# XBP-ST_morpho.net
KiCad netlist of a schematic drawn in EAGLE
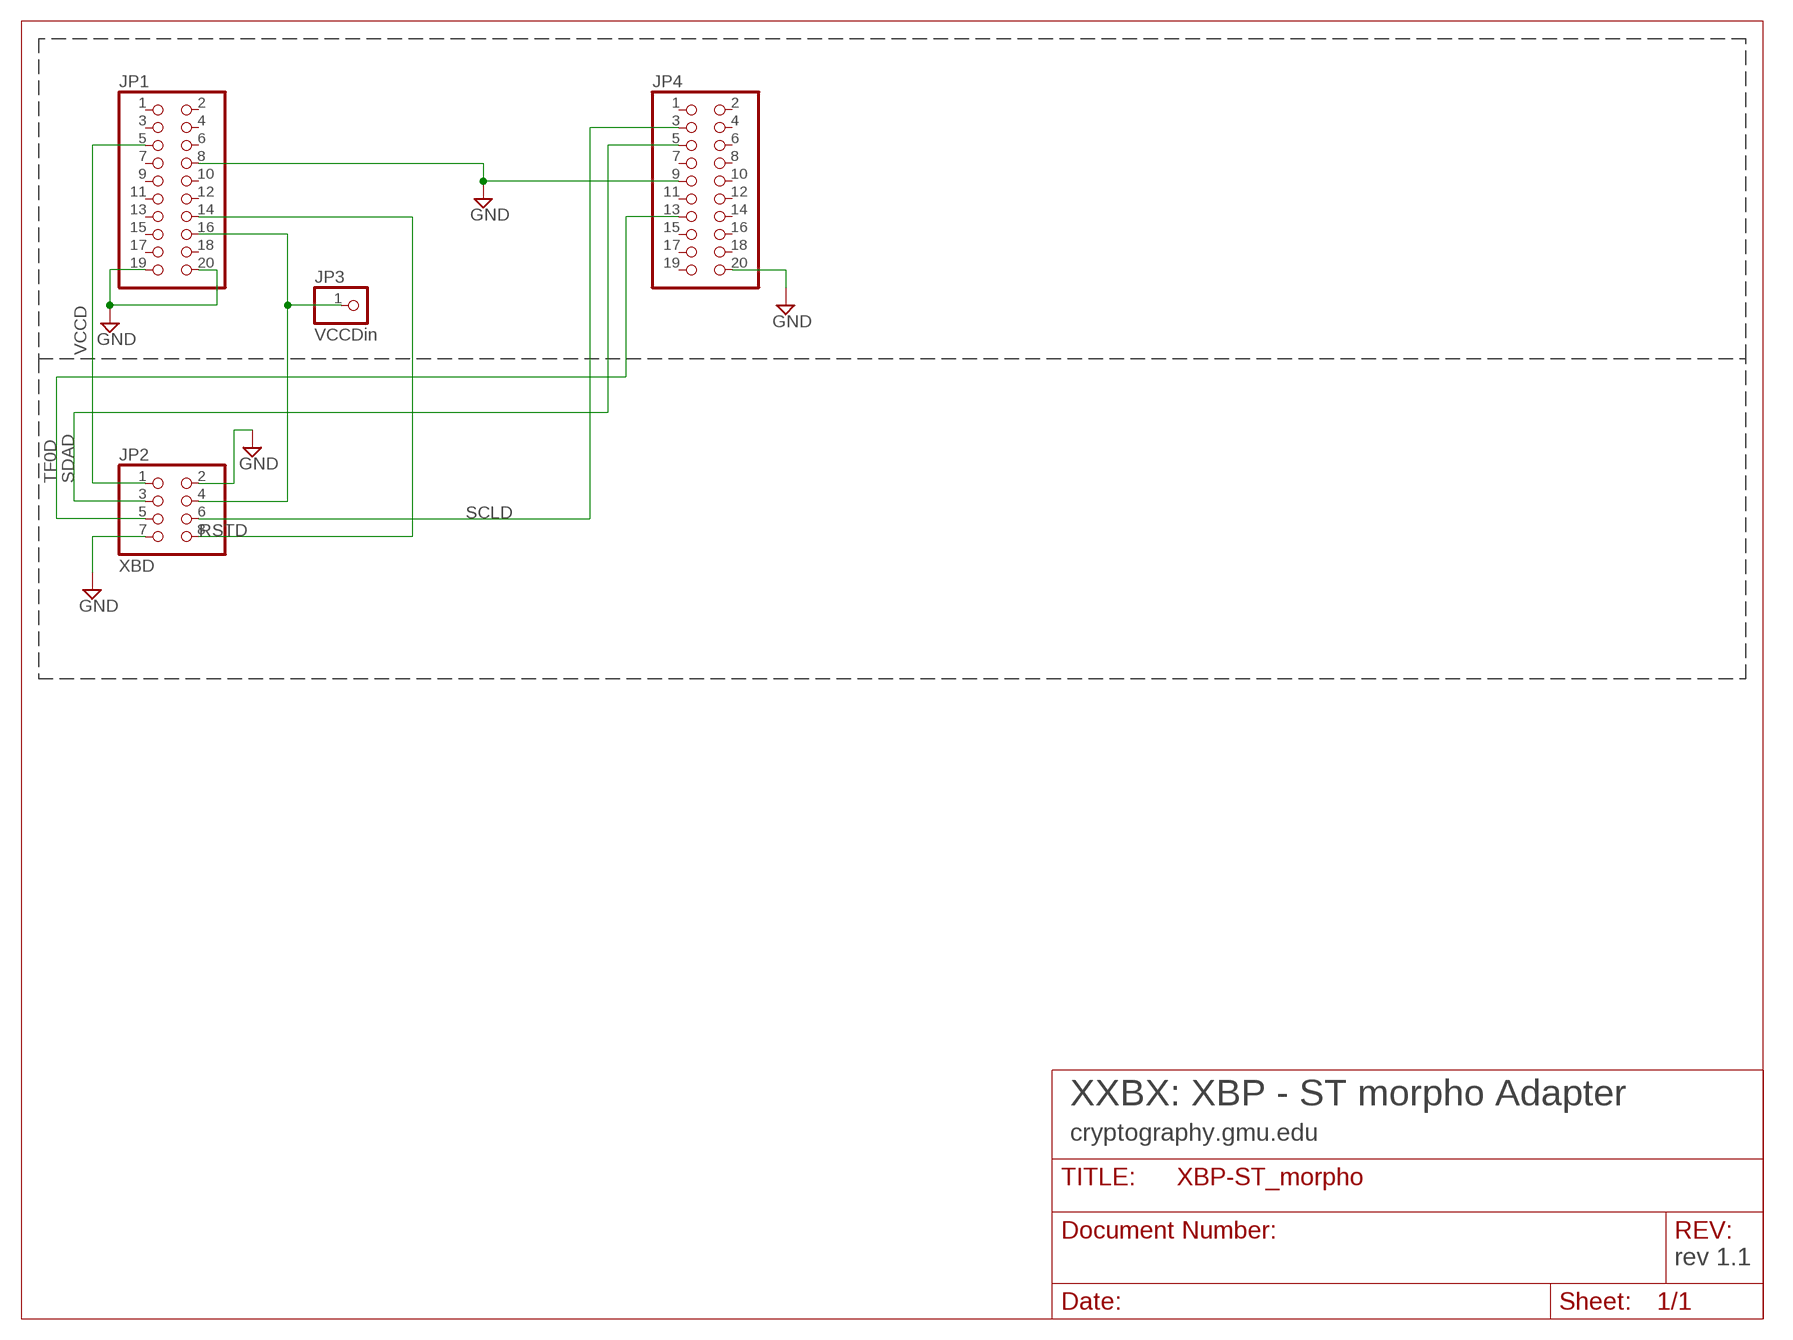
[diagram p0: schematic, sheet 1]

(export (version "E")
  (design (tool "Eeschema 10.0.6"))
  (components
    (comp (ref "JP1")
      (value "PINHD-2X10")
      (footprint "eagle-import:2X10")
      (libsource (lib "eagle-import") (part "PINHD-2X10"))
    )
    (comp (ref "JP2")
      (value "XBD")
      (footprint "eagle-import:2X04_90")
      (libsource (lib "eagle-import") (part "PINHD-2X4/90"))
    )
    (comp (ref "JP3")
      (value "VCCDin")
      (footprint "eagle-import:1X01")
      (libsource (lib "eagle-import") (part "PINHD-1X1"))
    )
    (comp (ref "JP4")
      (value "PINHD-2X10")
      (footprint "eagle-import:2X10")
      (libsource (lib "eagle-import") (part "PINHD-2X10"))
    )
  )
  (nets
    (net (code "1") (name "/RSTD") (class "Default")
      (node (ref "JP1") (pin "14") (pinfunction "14_14") (pintype "passive"))
      (node (ref "JP2") (pin "8") (pinfunction "8_8") (pintype "passive"))
    )
    (net (code "2") (name "/SCLD") (class "Default")
      (node (ref "JP2") (pin "6") (pinfunction "6_6") (pintype "passive"))
      (node (ref "JP4") (pin "3") (pinfunction "3_3") (pintype "passive"))
    )
    (net (code "3") (name "/SDAD") (class "Default")
      (node (ref "JP2") (pin "3") (pinfunction "3_3") (pintype "passive"))
      (node (ref "JP4") (pin "5") (pinfunction "5_5") (pintype "passive"))
    )
    (net (code "4") (name "/TF0D") (class "Default")
      (node (ref "JP2") (pin "5") (pinfunction "5_5") (pintype "passive"))
      (node (ref "JP4") (pin "13") (pinfunction "13_13") (pintype "passive"))
    )
    (net (code "5") (name "/VCCD") (class "Default")
      (node (ref "JP1") (pin "5") (pinfunction "5_5") (pintype "passive"))
      (node (ref "JP2") (pin "1") (pinfunction "1_1") (pintype "passive"))
    )
    (net (code "6") (name "GND") (class "Default")
      (node (ref "JP1") (pin "19") (pinfunction "19_19") (pintype "passive"))
      (node (ref "JP1") (pin "20") (pinfunction "20_20") (pintype "passive"))
      (node (ref "JP1") (pin "8") (pinfunction "8_8") (pintype "passive"))
      (node (ref "JP2") (pin "2") (pinfunction "2_2") (pintype "passive"))
      (node (ref "JP2") (pin "7") (pinfunction "7_7") (pintype "passive"))
      (node (ref "JP4") (pin "20") (pinfunction "20_20") (pintype "passive"))
      (node (ref "JP4") (pin "9") (pinfunction "9_9") (pintype "passive"))
    )
    (net (code "7") (name "Net-(JP1-Pad16)") (class "Default")
      (node (ref "JP1") (pin "16") (pinfunction "16_16") (pintype "passive"))
      (node (ref "JP2") (pin "4") (pinfunction "4_4") (pintype "passive"))
      (node (ref "JP3") (pin "1") (pinfunction "1_1") (pintype "passive"))
    )
    (net (code "8") (name "unconnected-(JP1-Pad1)") (class "Default")
      (node (ref "JP1") (pin "1") (pinfunction "1_1") (pintype "passive"))
    )
    (net (code "9") (name "unconnected-(JP1-Pad2)") (class "Default")
      (node (ref "JP1") (pin "2") (pinfunction "2_2") (pintype "passive"))
    )
    (net (code "10") (name "unconnected-(JP1-Pad3)") (class "Default")
      (node (ref "JP1") (pin "3") (pinfunction "3_3") (pintype "passive"))
    )
    (net (code "11") (name "unconnected-(JP1-Pad4)") (class "Default")
      (node (ref "JP1") (pin "4") (pinfunction "4_4") (pintype "passive"))
    )
    (net (code "12") (name "unconnected-(JP1-Pad6)") (class "Default")
      (node (ref "JP1") (pin "6") (pinfunction "6_6") (pintype "passive"))
    )
    (net (code "13") (name "unconnected-(JP1-Pad7)") (class "Default")
      (node (ref "JP1") (pin "7") (pinfunction "7_7") (pintype "passive"))
    )
    (net (code "14") (name "unconnected-(JP1-Pad9)") (class "Default")
      (node (ref "JP1") (pin "9") (pinfunction "9_9") (pintype "passive"))
    )
    (net (code "15") (name "unconnected-(JP1-Pad10)") (class "Default")
      (node (ref "JP1") (pin "10") (pinfunction "10_10") (pintype "passive"))
    )
    (net (code "16") (name "unconnected-(JP1-Pad11)") (class "Default")
      (node (ref "JP1") (pin "11") (pinfunction "11_11") (pintype "passive"))
    )
    (net (code "17") (name "unconnected-(JP1-Pad12)") (class "Default")
      (node (ref "JP1") (pin "12") (pinfunction "12_12") (pintype "passive"))
    )
    (net (code "18") (name "unconnected-(JP1-Pad13)") (class "Default")
      (node (ref "JP1") (pin "13") (pinfunction "13_13") (pintype "passive"))
    )
    (net (code "19") (name "unconnected-(JP1-Pad15)") (class "Default")
      (node (ref "JP1") (pin "15") (pinfunction "15_15") (pintype "passive"))
    )
    (net (code "20") (name "unconnected-(JP1-Pad17)") (class "Default")
      (node (ref "JP1") (pin "17") (pinfunction "17_17") (pintype "passive"))
    )
    (net (code "21") (name "unconnected-(JP1-Pad18)") (class "Default")
      (node (ref "JP1") (pin "18") (pinfunction "18_18") (pintype "passive"))
    )
    (net (code "22") (name "unconnected-(JP4-Pad1)") (class "Default")
      (node (ref "JP4") (pin "1") (pinfunction "1_1") (pintype "passive"))
    )
    (net (code "23") (name "unconnected-(JP4-Pad2)") (class "Default")
      (node (ref "JP4") (pin "2") (pinfunction "2_2") (pintype "passive"))
    )
    (net (code "24") (name "unconnected-(JP4-Pad4)") (class "Default")
      (node (ref "JP4") (pin "4") (pinfunction "4_4") (pintype "passive"))
    )
    (net (code "25") (name "unconnected-(JP4-Pad6)") (class "Default")
      (node (ref "JP4") (pin "6") (pinfunction "6_6") (pintype "passive"))
    )
    (net (code "26") (name "unconnected-(JP4-Pad7)") (class "Default")
      (node (ref "JP4") (pin "7") (pinfunction "7_7") (pintype "passive"))
    )
    (net (code "27") (name "unconnected-(JP4-Pad8)") (class "Default")
      (node (ref "JP4") (pin "8") (pinfunction "8_8") (pintype "passive"))
    )
    (net (code "28") (name "unconnected-(JP4-Pad10)") (class "Default")
      (node (ref "JP4") (pin "10") (pinfunction "10_10") (pintype "passive"))
    )
    (net (code "29") (name "unconnected-(JP4-Pad11)") (class "Default")
      (node (ref "JP4") (pin "11") (pinfunction "11_11") (pintype "passive"))
    )
    (net (code "30") (name "unconnected-(JP4-Pad12)") (class "Default")
      (node (ref "JP4") (pin "12") (pinfunction "12_12") (pintype "passive"))
    )
    (net (code "31") (name "unconnected-(JP4-Pad14)") (class "Default")
      (node (ref "JP4") (pin "14") (pinfunction "14_14") (pintype "passive"))
    )
    (net (code "32") (name "unconnected-(JP4-Pad15)") (class "Default")
      (node (ref "JP4") (pin "15") (pinfunction "15_15") (pintype "passive"))
    )
    (net (code "33") (name "unconnected-(JP4-Pad16)") (class "Default")
      (node (ref "JP4") (pin "16") (pinfunction "16_16") (pintype "passive"))
    )
    (net (code "34") (name "unconnected-(JP4-Pad17)") (class "Default")
      (node (ref "JP4") (pin "17") (pinfunction "17_17") (pintype "passive"))
    )
    (net (code "35") (name "unconnected-(JP4-Pad18)") (class "Default")
      (node (ref "JP4") (pin "18") (pinfunction "18_18") (pintype "passive"))
    )
    (net (code "36") (name "unconnected-(JP4-Pad19)") (class "Default")
      (node (ref "JP4") (pin "19") (pinfunction "19_19") (pintype "passive"))
    )
  )
)
